# SmoothieDriverDualDC.net
KiCad netlist of a schematic drawn in EAGLE
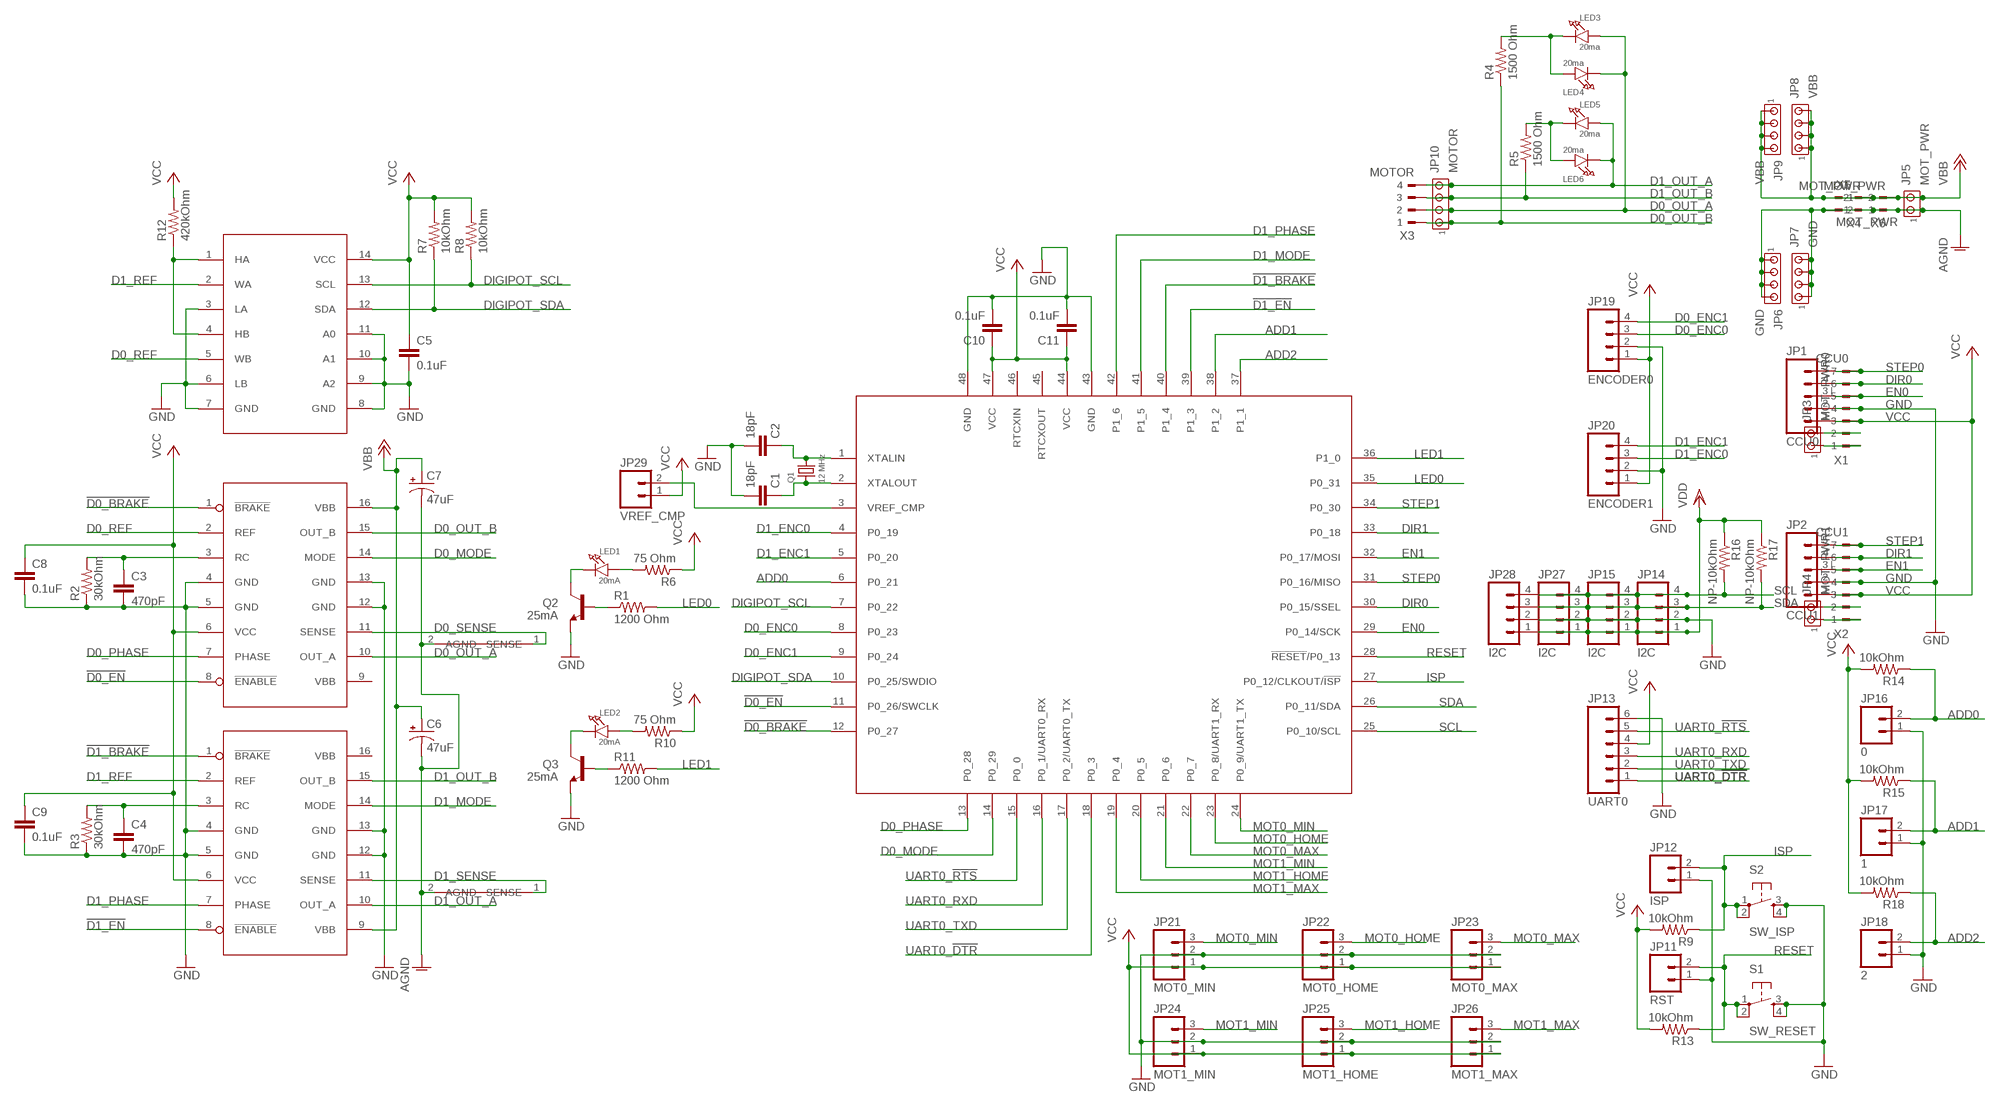
[diagram p0: schematic, sheet 1]

(export (version "E")
  (design (tool "Eeschema 10.0.6"))
  (components
    (comp (ref "C1")
      (value "18pF")
      (footprint "eagle-import:C0603")
      (libsource (lib "eagle-import") (part "C-EUC0603"))
    )
    (comp (ref "C2")
      (value "18pF")
      (footprint "eagle-import:C0603")
      (libsource (lib "eagle-import") (part "C-EUC0603"))
    )
    (comp (ref "C3")
      (value "470pF")
      (footprint "eagle-import:C0603")
      (libsource (lib "eagle-import") (part "C-EUC0603"))
    )
    (comp (ref "C4")
      (value "470pF")
      (footprint "eagle-import:C0603")
      (libsource (lib "eagle-import") (part "C-EUC0603"))
    )
    (comp (ref "C5")
      (value "0.1uF")
      (footprint "eagle-import:C0603")
      (libsource (lib "eagle-import") (part "C-EUC0603"))
    )
    (comp (ref "C6")
      (value "47uF")
      (footprint "eagle-import:PANASONIC_D")
      (libsource (lib "eagle-import") (part "CAP_POLD"))
    )
    (comp (ref "C7")
      (value "47uF")
      (footprint "eagle-import:PANASONIC_D")
      (libsource (lib "eagle-import") (part "CAP_POLD"))
    )
    (comp (ref "C8")
      (value "0.1uF")
      (footprint "eagle-import:C0603")
      (libsource (lib "eagle-import") (part "C-EUC0603"))
    )
    (comp (ref "C9")
      (value "0.1uF")
      (footprint "eagle-import:C0603")
      (libsource (lib "eagle-import") (part "C-EUC0603"))
    )
    (comp (ref "C10")
      (value "0.1uF")
      (footprint "eagle-import:C0603")
      (libsource (lib "eagle-import") (part "C-EUC0603"))
    )
    (comp (ref "C11")
      (value "0.1uF")
      (footprint "eagle-import:C0603")
      (libsource (lib "eagle-import") (part "C-EUC0603"))
    )
    (comp (ref "JP1")
      (value "CCU0")
      (footprint "eagle-import:1X05")
      (libsource (lib "eagle-import") (part "M05PTH"))
    )
    (comp (ref "JP2")
      (value "CCU1")
      (footprint "eagle-import:1X05")
      (libsource (lib "eagle-import") (part "M05PTH"))
    )
    (comp (ref "JP3")
      (value "MOT_PWR0")
      (footprint "eagle-import:10X02MTA")
      (libsource (lib "eagle-import") (part "MTA02-100"))
    )
    (comp (ref "JP4")
      (value "MOT_PWR1")
      (footprint "eagle-import:10X02MTA")
      (libsource (lib "eagle-import") (part "MTA02-100"))
    )
    (comp (ref "JP5")
      (value "MOT_PWR")
      (footprint "eagle-import:10X02MTA")
      (libsource (lib "eagle-import") (part "MTA02-100"))
    )
    (comp (ref "JP6")
      (value "GND")
      (footprint "eagle-import:10X04MTA")
      (libsource (lib "eagle-import") (part "MTA04-100"))
    )
    (comp (ref "JP7")
      (value "GND")
      (footprint "eagle-import:10X04MTA")
      (libsource (lib "eagle-import") (part "MTA04-100"))
    )
    (comp (ref "JP8")
      (value "VBB")
      (footprint "eagle-import:10X04MTA")
      (libsource (lib "eagle-import") (part "MTA04-100"))
    )
    (comp (ref "JP9")
      (value "VBB")
      (footprint "eagle-import:10X04MTA")
      (libsource (lib "eagle-import") (part "MTA04-100"))
    )
    (comp (ref "JP10")
      (value "MOTOR")
      (footprint "eagle-import:10X04MTA")
      (libsource (lib "eagle-import") (part "MTA04-100"))
    )
    (comp (ref "JP11")
      (value "RST")
      (footprint "eagle-import:1X02")
      (libsource (lib "eagle-import") (part "M02PTH"))
    )
    (comp (ref "JP12")
      (value "ISP")
      (footprint "eagle-import:1X02")
      (libsource (lib "eagle-import") (part "M02PTH"))
    )
    (comp (ref "JP13")
      (value "UART0")
      (footprint "eagle-import:1X06")
      (libsource (lib "eagle-import") (part "M06SIP"))
    )
    (comp (ref "JP14")
      (value "I2C")
      (footprint "eagle-import:1X04")
      (libsource (lib "eagle-import") (part "M04PTH"))
    )
    (comp (ref "JP15")
      (value "I2C")
      (footprint "eagle-import:1X04")
      (libsource (lib "eagle-import") (part "M04PTH"))
    )
    (comp (ref "JP16")
      (value "0")
      (footprint "eagle-import:1X02")
      (libsource (lib "eagle-import") (part "M02PTH"))
    )
    (comp (ref "JP17")
      (value "1")
      (footprint "eagle-import:1X02")
      (libsource (lib "eagle-import") (part "M02PTH"))
    )
    (comp (ref "JP18")
      (value "2")
      (footprint "eagle-import:1X02")
      (libsource (lib "eagle-import") (part "M02PTH"))
    )
    (comp (ref "JP19")
      (value "ENCODER0")
      (footprint "eagle-import:1X04")
      (libsource (lib "eagle-import") (part "M04PTH"))
    )
    (comp (ref "JP20")
      (value "ENCODER1")
      (footprint "eagle-import:1X04")
      (libsource (lib "eagle-import") (part "M04PTH"))
    )
    (comp (ref "JP21")
      (value "MOT0_MIN")
      (footprint "eagle-import:1X03")
      (libsource (lib "eagle-import") (part "M03PTH"))
    )
    (comp (ref "JP22")
      (value "MOT0_HOME")
      (footprint "eagle-import:1X03")
      (libsource (lib "eagle-import") (part "M03PTH"))
    )
    (comp (ref "JP23")
      (value "MOT0_MAX")
      (footprint "eagle-import:1X03")
      (libsource (lib "eagle-import") (part "M03PTH"))
    )
    (comp (ref "JP24")
      (value "MOT1_MIN")
      (footprint "eagle-import:1X03")
      (libsource (lib "eagle-import") (part "M03PTH"))
    )
    (comp (ref "JP25")
      (value "MOT1_HOME")
      (footprint "eagle-import:1X03")
      (libsource (lib "eagle-import") (part "M03PTH"))
    )
    (comp (ref "JP26")
      (value "MOT1_MAX")
      (footprint "eagle-import:1X03")
      (libsource (lib "eagle-import") (part "M03PTH"))
    )
    (comp (ref "JP27")
      (value "I2C")
      (footprint "eagle-import:1X04")
      (libsource (lib "eagle-import") (part "M04PTH"))
    )
    (comp (ref "JP28")
      (value "I2C")
      (footprint "eagle-import:1X04")
      (libsource (lib "eagle-import") (part "M04PTH"))
    )
    (comp (ref "JP29")
      (value "VREF_CMP")
      (footprint "eagle-import:1X02")
      (libsource (lib "eagle-import") (part "M02PTH"))
    )
    (comp (ref "LED1")
      (value "20mA")
      (footprint "eagle-import:CHIPLED_0805")
      (libsource (lib "eagle-import") (part "LED0805"))
    )
    (comp (ref "LED2")
      (value "20mA")
      (footprint "eagle-import:CHIPLED_0805")
      (libsource (lib "eagle-import") (part "LED0805"))
    )
    (comp (ref "LED3")
      (value "20ma")
      (footprint "eagle-import:CHIPLED_0805")
      (libsource (lib "eagle-import") (part "LED0805"))
    )
    (comp (ref "LED4")
      (value "20ma")
      (footprint "eagle-import:CHIPLED_0805")
      (libsource (lib "eagle-import") (part "LED0805"))
    )
    (comp (ref "LED5")
      (value "20ma")
      (footprint "eagle-import:CHIPLED_0805")
      (libsource (lib "eagle-import") (part "LED0805"))
    )
    (comp (ref "LED6")
      (value "20ma")
      (footprint "eagle-import:CHIPLED_0805")
      (libsource (lib "eagle-import") (part "LED0805"))
    )
    (comp (ref "MCU1")
      (value "LPC1227")
      (footprint "eagle-import:LQFP48")
      (libsource (lib "eagle-import") (part "LPC1227"))
    )
    (comp (ref "Q1")
      (value "12 MHz")
      (footprint "eagle-import:CRYSTAL_3.2X2.5")
      (libsource (lib "eagle-import") (part "CRYSTALTHIN"))
    )
    (comp (ref "Q2")
      (value "25mA")
      (footprint "eagle-import:SOT23")
      (libsource (lib "eagle-import") (part "TRANSISTOR_NPNSOT23"))
    )
    (comp (ref "Q3")
      (value "25mA")
      (footprint "eagle-import:SOT23")
      (libsource (lib "eagle-import") (part "TRANSISTOR_NPNSOT23"))
    )
    (comp (ref "R1")
      (value "1200 Ohm")
      (footprint "eagle-import:R0603")
      (libsource (lib "eagle-import") (part "R-US_R0603"))
    )
    (comp (ref "R2")
      (value "30kOhm")
      (footprint "eagle-import:R0603")
      (libsource (lib "eagle-import") (part "R-US_R0603"))
    )
    (comp (ref "R3")
      (value "30kOhm")
      (footprint "eagle-import:R0603")
      (libsource (lib "eagle-import") (part "R-US_R0603"))
    )
    (comp (ref "R4")
      (value "1500 Ohm")
      (footprint "eagle-import:R0603")
      (libsource (lib "eagle-import") (part "R-US_R0603"))
    )
    (comp (ref "R5")
      (value "1500 Ohm")
      (footprint "eagle-import:R0603")
      (libsource (lib "eagle-import") (part "R-US_R0603"))
    )
    (comp (ref "R6")
      (value "75 Ohm")
      (footprint "eagle-import:R0603")
      (libsource (lib "eagle-import") (part "R-US_R0603"))
    )
    (comp (ref "R7")
      (value "10kOhm")
      (footprint "eagle-import:R0603")
      (libsource (lib "eagle-import") (part "R-US_R0603"))
    )
    (comp (ref "R8")
      (value "10kOhm")
      (footprint "eagle-import:R0603")
      (libsource (lib "eagle-import") (part "R-US_R0603"))
    )
    (comp (ref "R9")
      (value "10kOhm")
      (footprint "eagle-import:R0603")
      (libsource (lib "eagle-import") (part "R-US_R0603"))
    )
    (comp (ref "R10")
      (value "75 Ohm")
      (footprint "eagle-import:R0603")
      (libsource (lib "eagle-import") (part "R-US_R0603"))
    )
    (comp (ref "R11")
      (value "1200 Ohm")
      (footprint "eagle-import:R0603")
      (libsource (lib "eagle-import") (part "R-US_R0603"))
    )
    (comp (ref "R12")
      (value "420kOhm")
      (footprint "eagle-import:R0603")
      (libsource (lib "eagle-import") (part "R-US_R0603"))
    )
    (comp (ref "R13")
      (value "10kOhm")
      (footprint "eagle-import:R0603")
      (libsource (lib "eagle-import") (part "R-US_R0603"))
    )
    (comp (ref "R14")
      (value "10kOhm")
      (footprint "eagle-import:R0603")
      (libsource (lib "eagle-import") (part "R-US_R0603"))
    )
    (comp (ref "R15")
      (value "10kOhm")
      (footprint "eagle-import:R0603")
      (libsource (lib "eagle-import") (part "R-US_R0603"))
    )
    (comp (ref "R16")
      (value "NP-10kOhm")
      (footprint "eagle-import:R0603")
      (libsource (lib "eagle-import") (part "R-US_R0603"))
    )
    (comp (ref "R17")
      (value "NP-10kOhm")
      (footprint "eagle-import:R0603")
      (libsource (lib "eagle-import") (part "R-US_R0603"))
    )
    (comp (ref "R18")
      (value "10kOhm")
      (footprint "eagle-import:R0603")
      (libsource (lib "eagle-import") (part "R-US_R0603"))
    )
    (comp (ref "S1")
      (value "SW_RESET")
      (footprint "eagle-import:TACTILE_SWITCH_SMD")
      (libsource (lib "eagle-import") (part "TAC_SWITCHSMD"))
    )
    (comp (ref "S2")
      (value "SW_ISP")
      (footprint "eagle-import:TACTILE_SWITCH_SMD")
      (libsource (lib "eagle-import") (part "TAC_SWITCHSMD"))
    )
    (comp (ref "U$1")
      (value "CONNECTOR")
      (footprint "eagle-import:CONNECT")
      (libsource (lib "eagle-import") (part "CONNECTOR"))
    )
    (comp (ref "U$2")
      (value "CONNECTOR")
      (footprint "eagle-import:CONNECT")
      (libsource (lib "eagle-import") (part "CONNECTOR"))
    )
    (comp (ref "U1")
      (value "MAX5387-50kOhm")
      (footprint "eagle-import:TSSOP14")
      (libsource (lib "eagle-import") (part "MAX5387"))
    )
    (comp (ref "U2")
      (value "A4973")
      (footprint "eagle-import:SO16L")
      (libsource (lib "eagle-import") (part "A4973"))
    )
    (comp (ref "U3")
      (value "A4973")
      (footprint "eagle-import:SO16L")
      (libsource (lib "eagle-import") (part "A4973"))
    )
    (comp (ref "X1")
      (value "CCU0")
      (footprint "eagle-import:180G-7")
      (libsource (lib "eagle-import") (part "180G-7"))
    )
    (comp (ref "X2")
      (value "CCU1")
      (footprint "eagle-import:180G-7")
      (libsource (lib "eagle-import") (part "180G-7"))
    )
    (comp (ref "X3")
      (value "MOTOR")
      (footprint "eagle-import:180G-4")
      (libsource (lib "eagle-import") (part "180G-4"))
    )
    (comp (ref "X4")
      (value "MOT_PWR")
      (footprint "eagle-import:180G-2")
      (fields (field (name "OC_FARNELL") "unknown") (field (name "OC_NEWARK") "unknown"))
      (libsource (lib "eagle-import") (part "180G-2"))
    )
    (comp (ref "X5")
      (value "MOT_PWR")
      (footprint "eagle-import:180G-2")
      (fields (field (name "OC_FARNELL") "unknown") (field (name "OC_NEWARK") "unknown"))
      (libsource (lib "eagle-import") (part "180G-2"))
    )
    (comp (ref "X6")
      (value "MOT_PWR")
      (footprint "eagle-import:180G-2")
      (libsource (lib "eagle-import") (part "180G-2"))
    )
  )
  (nets
    (net (code "1") (name "/ADD0") (class "Default")
      (node (ref "JP16") (pin "2") (pinfunction "2_2") (pintype "passive"))
      (node (ref "MCU1") (pin "6") (pinfunction "P0_21_6") (pintype "bidirectional"))
      (node (ref "R14") (pin "1") (pinfunction "1_1") (pintype "passive"))
    )
    (net (code "2") (name "/ADD1") (class "Default")
      (node (ref "JP17") (pin "2") (pinfunction "2_2") (pintype "passive"))
      (node (ref "MCU1") (pin "38") (pinfunction "P1_2_38") (pintype "bidirectional"))
      (node (ref "R15") (pin "1") (pinfunction "1_1") (pintype "passive"))
    )
    (net (code "3") (name "/ADD2") (class "Default")
      (node (ref "JP18") (pin "2") (pinfunction "2_2") (pintype "passive"))
      (node (ref "MCU1") (pin "37") (pinfunction "P1_1_37") (pintype "bidirectional"))
      (node (ref "R18") (pin "1") (pinfunction "1_1") (pintype "passive"))
    )
    (net (code "4") (name "/D0_ENC0") (class "Default")
      (node (ref "JP19") (pin "3") (pinfunction "3_3") (pintype "passive"))
      (node (ref "MCU1") (pin "8") (pinfunction "P0_23_8") (pintype "bidirectional"))
    )
    (net (code "5") (name "/D0_ENC1") (class "Default")
      (node (ref "JP19") (pin "4") (pinfunction "4_4") (pintype "passive"))
      (node (ref "MCU1") (pin "9") (pinfunction "P0_24_9") (pintype "bidirectional"))
    )
    (net (code "6") (name "/D0_MODE") (class "Default")
      (node (ref "MCU1") (pin "14") (pinfunction "P0_29_14") (pintype "bidirectional"))
      (node (ref "U2") (pin "14") (pinfunction "MODE_14") (pintype "input"))
    )
    (net (code "7") (name "/D0_OUT_A") (class "Default")
      (node (ref "JP10") (pin "2") (pinfunction "2_2") (pintype "passive"))
      (node (ref "LED3") (pin "A") (pinfunction "A_A") (pintype "passive"))
      (node (ref "LED4") (pin "C") (pinfunction "C_C") (pintype "passive"))
      (node (ref "U2") (pin "10") (pinfunction "OUT_A_10") (pintype "output"))
      (node (ref "X3") (pin "2") (pinfunction "2_2") (pintype "passive"))
    )
    (net (code "8") (name "/D0_OUT_B") (class "Default")
      (node (ref "JP10") (pin "1") (pinfunction "1_1") (pintype "passive"))
      (node (ref "R4") (pin "1") (pinfunction "1_1") (pintype "passive"))
      (node (ref "U2") (pin "15") (pinfunction "OUT_B_15") (pintype "output"))
      (node (ref "X3") (pin "1") (pinfunction "1_1") (pintype "passive"))
    )
    (net (code "9") (name "/D0_PHASE") (class "Default")
      (node (ref "MCU1") (pin "13") (pinfunction "P0_28_13") (pintype "bidirectional"))
      (node (ref "U2") (pin "7") (pinfunction "PHASE_7") (pintype "input"))
    )
    (net (code "10") (name "/D0_REF") (class "Default")
      (node (ref "U1") (pin "5") (pinfunction "WB_5") (pintype "passive"))
      (node (ref "U2") (pin "2") (pinfunction "REF_2") (pintype "input"))
    )
    (net (code "11") (name "/D0_SENSE") (class "Default")
      (node (ref "U$2") (pin "1") (pinfunction "SENSE_1") (pintype "bidirectional"))
      (node (ref "U2") (pin "11") (pinfunction "SENSE_11") (pintype "bidirectional"))
    )
    (net (code "12") (name "/D1_ENC0") (class "Default")
      (node (ref "JP20") (pin "3") (pinfunction "3_3") (pintype "passive"))
      (node (ref "MCU1") (pin "4") (pinfunction "P0_19_4") (pintype "bidirectional"))
    )
    (net (code "13") (name "/D1_ENC1") (class "Default")
      (node (ref "JP20") (pin "4") (pinfunction "4_4") (pintype "passive"))
      (node (ref "MCU1") (pin "5") (pinfunction "P0_20_5") (pintype "bidirectional"))
    )
    (net (code "14") (name "/D1_MODE") (class "Default")
      (node (ref "MCU1") (pin "41") (pinfunction "P1_5_41") (pintype "bidirectional"))
      (node (ref "U3") (pin "14") (pinfunction "MODE_14") (pintype "input"))
    )
    (net (code "15") (name "/D1_OUT_A") (class "Default")
      (node (ref "JP10") (pin "4") (pinfunction "4_4") (pintype "passive"))
      (node (ref "LED5") (pin "A") (pinfunction "A_A") (pintype "passive"))
      (node (ref "LED6") (pin "C") (pinfunction "C_C") (pintype "passive"))
      (node (ref "U3") (pin "10") (pinfunction "OUT_A_10") (pintype "output"))
      (node (ref "X3") (pin "4") (pinfunction "4_4") (pintype "passive"))
    )
    (net (code "16") (name "/D1_OUT_B") (class "Default")
      (node (ref "JP10") (pin "3") (pinfunction "3_3") (pintype "passive"))
      (node (ref "R5") (pin "1") (pinfunction "1_1") (pintype "passive"))
      (node (ref "U3") (pin "15") (pinfunction "OUT_B_15") (pintype "output"))
      (node (ref "X3") (pin "3") (pinfunction "3_3") (pintype "passive"))
    )
    (net (code "17") (name "/D1_PHASE") (class "Default")
      (node (ref "MCU1") (pin "42") (pinfunction "P1_6_42") (pintype "bidirectional"))
      (node (ref "U3") (pin "7") (pinfunction "PHASE_7") (pintype "input"))
    )
    (net (code "18") (name "/D1_REF") (class "Default")
      (node (ref "U1") (pin "2") (pinfunction "WA_2") (pintype "passive"))
      (node (ref "U3") (pin "2") (pinfunction "REF_2") (pintype "input"))
    )
    (net (code "19") (name "/D1_SENSE") (class "Default")
      (node (ref "U$1") (pin "1") (pinfunction "SENSE_1") (pintype "bidirectional"))
      (node (ref "U3") (pin "11") (pinfunction "SENSE_11") (pintype "bidirectional"))
    )
    (net (code "20") (name "/DIGIPOT_SCL") (class "Default")
      (node (ref "MCU1") (pin "7") (pinfunction "P0_22_7") (pintype "bidirectional"))
      (node (ref "R8") (pin "1") (pinfunction "1_1") (pintype "passive"))
      (node (ref "U1") (pin "13") (pinfunction "SCL_13") (pintype "input"))
    )
    (net (code "21") (name "/DIGIPOT_SDA") (class "Default")
      (node (ref "MCU1") (pin "10") (pinfunction "P0_25/SWDIO_10") (pintype "bidirectional"))
      (node (ref "R7") (pin "1") (pinfunction "1_1") (pintype "passive"))
      (node (ref "U1") (pin "12") (pinfunction "SDA_12") (pintype "bidirectional"))
    )
    (net (code "22") (name "/DIR0") (class "Default")
      (node (ref "JP1") (pin "4") (pinfunction "4_4") (pintype "passive"))
      (node (ref "MCU1") (pin "30") (pinfunction "P0_15/SSEL_30") (pintype "bidirectional"))
      (node (ref "X1") (pin "6") (pinfunction "6_6") (pintype "passive"))
    )
    (net (code "23") (name "/DIR1") (class "Default")
      (node (ref "JP2") (pin "4") (pinfunction "4_4") (pintype "passive"))
      (node (ref "MCU1") (pin "33") (pinfunction "P0_18_33") (pintype "bidirectional"))
      (node (ref "X2") (pin "6") (pinfunction "6_6") (pintype "passive"))
    )
    (net (code "24") (name "/EN0") (class "Default")
      (node (ref "JP1") (pin "3") (pinfunction "3_3") (pintype "passive"))
      (node (ref "MCU1") (pin "29") (pinfunction "P0_14/SCK_29") (pintype "bidirectional"))
      (node (ref "X1") (pin "5") (pinfunction "5_5") (pintype "passive"))
    )
    (net (code "25") (name "/EN1") (class "Default")
      (node (ref "JP2") (pin "3") (pinfunction "3_3") (pintype "passive"))
      (node (ref "MCU1") (pin "32") (pinfunction "P0_17/MOSI_32") (pintype "bidirectional"))
      (node (ref "X2") (pin "5") (pinfunction "5_5") (pintype "passive"))
    )
    (net (code "26") (name "/ISP") (class "Default")
      (node (ref "JP12") (pin "2") (pinfunction "2_2") (pintype "passive"))
      (node (ref "MCU1") (pin "27") (pinfunction "P0_12/CLKOUT/~{ISP}_27") (pintype "bidirectional"))
      (node (ref "R9") (pin "1") (pinfunction "1_1") (pintype "passive"))
      (node (ref "S2") (pin "1") (pinfunction "1_1") (pintype "passive"))
      (node (ref "S2") (pin "2") (pinfunction "2_2") (pintype "passive"))
    )
    (net (code "27") (name "/LED0") (class "Default")
      (node (ref "MCU1") (pin "35") (pinfunction "P0_31_35") (pintype "bidirectional"))
      (node (ref "R1") (pin "2") (pinfunction "2_2") (pintype "passive"))
    )
    (net (code "28") (name "/LED1") (class "Default")
      (node (ref "MCU1") (pin "36") (pinfunction "P1_0_36") (pintype "bidirectional"))
      (node (ref "R11") (pin "2") (pinfunction "2_2") (pintype "passive"))
    )
    (net (code "29") (name "/MOT0_HOME") (class "Default")
      (node (ref "JP22") (pin "3") (pinfunction "3_3") (pintype "passive"))
      (node (ref "MCU1") (pin "23") (pinfunction "P0_8/UART1_RX_23") (pintype "bidirectional"))
    )
    (net (code "30") (name "/MOT0_MAX") (class "Default")
      (node (ref "JP23") (pin "3") (pinfunction "3_3") (pintype "passive"))
      (node (ref "MCU1") (pin "22") (pinfunction "P0_7_22") (pintype "bidirectional"))
    )
    (net (code "31") (name "/MOT0_MIN") (class "Default")
      (node (ref "JP21") (pin "3") (pinfunction "3_3") (pintype "passive"))
      (node (ref "MCU1") (pin "24") (pinfunction "P0_9/UART1_TX_24") (pintype "bidirectional"))
    )
    (net (code "32") (name "/MOT1_HOME") (class "Default")
      (node (ref "JP25") (pin "3") (pinfunction "3_3") (pintype "passive"))
      (node (ref "MCU1") (pin "20") (pinfunction "P0_5_20") (pintype "bidirectional"))
    )
    (net (code "33") (name "/MOT1_MAX") (class "Default")
      (node (ref "JP26") (pin "3") (pinfunction "3_3") (pintype "passive"))
      (node (ref "MCU1") (pin "19") (pinfunction "P0_4_19") (pintype "bidirectional"))
    )
    (net (code "34") (name "/MOT1_MIN") (class "Default")
      (node (ref "JP24") (pin "3") (pinfunction "3_3") (pintype "passive"))
      (node (ref "MCU1") (pin "21") (pinfunction "P0_6_21") (pintype "bidirectional"))
    )
    (net (code "35") (name "/RESET") (class "Default")
      (node (ref "JP11") (pin "2") (pinfunction "2_2") (pintype "passive"))
      (node (ref "MCU1") (pin "28") (pinfunction "~{RESET}/P0_13_28") (pintype "bidirectional"))
      (node (ref "R13") (pin "1") (pinfunction "1_1") (pintype "passive"))
      (node (ref "S1") (pin "1") (pinfunction "1_1") (pintype "passive"))
      (node (ref "S1") (pin "2") (pinfunction "2_2") (pintype "passive"))
    )
    (net (code "36") (name "/SCL") (class "Default")
      (node (ref "JP14") (pin "4") (pinfunction "4_4") (pintype "passive"))
      (node (ref "JP15") (pin "4") (pinfunction "4_4") (pintype "passive"))
      (node (ref "JP27") (pin "4") (pinfunction "4_4") (pintype "passive"))
      (node (ref "JP28") (pin "4") (pinfunction "4_4") (pintype "passive"))
      (node (ref "MCU1") (pin "25") (pinfunction "P0_10/SCL_25") (pintype "bidirectional"))
      (node (ref "R16") (pin "2") (pinfunction "2_2") (pintype "passive"))
    )
    (net (code "37") (name "/SDA") (class "Default")
      (node (ref "JP14") (pin "3") (pinfunction "3_3") (pintype "passive"))
      (node (ref "JP15") (pin "3") (pinfunction "3_3") (pintype "passive"))
      (node (ref "JP27") (pin "3") (pinfunction "3_3") (pintype "passive"))
      (node (ref "JP28") (pin "3") (pinfunction "3_3") (pintype "passive"))
      (node (ref "MCU1") (pin "26") (pinfunction "P0_11/SDA_26") (pintype "bidirectional"))
      (node (ref "R17") (pin "2") (pinfunction "2_2") (pintype "passive"))
    )
    (net (code "38") (name "/STEP0") (class "Default")
      (node (ref "JP1") (pin "5") (pinfunction "5_5") (pintype "passive"))
      (node (ref "MCU1") (pin "31") (pinfunction "P0_16/MISO_31") (pintype "bidirectional"))
      (node (ref "X1") (pin "7") (pinfunction "7_7") (pintype "passive"))
    )
    (net (code "39") (name "/STEP1") (class "Default")
      (node (ref "JP2") (pin "5") (pinfunction "5_5") (pintype "passive"))
      (node (ref "MCU1") (pin "34") (pinfunction "P0_30_34") (pintype "bidirectional"))
      (node (ref "X2") (pin "7") (pinfunction "7_7") (pintype "passive"))
    )
    (net (code "40") (name "/UART0_RXD") (class "Default")
      (node (ref "JP13") (pin "3") (pinfunction "3_3") (pintype "passive"))
      (node (ref "MCU1") (pin "16") (pinfunction "P0_1/UART0_RX_16") (pintype "bidirectional"))
    )
    (net (code "41") (name "/UART0_TXD") (class "Default")
      (node (ref "JP13") (pin "2") (pinfunction "2_2") (pintype "passive"))
      (node (ref "MCU1") (pin "17") (pinfunction "P0_2/UART0_TX_17") (pintype "bidirectional"))
    )
    (net (code "42") (name "/UART0_~{DTR}") (class "Default")
      (node (ref "JP13") (pin "1") (pinfunction "1_1") (pintype "passive"))
      (node (ref "MCU1") (pin "18") (pinfunction "P0_3_18") (pintype "bidirectional"))
    )
    (net (code "43") (name "/UART0_~{RTS}") (class "Default")
      (node (ref "JP13") (pin "5") (pinfunction "5_5") (pintype "passive"))
      (node (ref "MCU1") (pin "15") (pinfunction "P0_0_15") (pintype "bidirectional"))
    )
    (net (code "44") (name "/~{D0_BRAKE}") (class "Default")
      (node (ref "MCU1") (pin "12") (pinfunction "P0_27_12") (pintype "bidirectional"))
      (node (ref "U2") (pin "1") (pinfunction "~{BRAKE}_1") (pintype "input"))
    )
    (net (code "45") (name "/~{D0_EN}") (class "Default")
      (node (ref "MCU1") (pin "11") (pinfunction "P0_26/SWCLK_11") (pintype "bidirectional"))
      (node (ref "U2") (pin "8") (pinfunction "~{ENABLE}_8") (pintype "input"))
    )
    (net (code "46") (name "/~{D1_BRAKE}") (class "Default")
      (node (ref "MCU1") (pin "40") (pinfunction "P1_4_40") (pintype "bidirectional"))
      (node (ref "U3") (pin "1") (pinfunction "~{BRAKE}_1") (pintype "input"))
    )
    (net (code "47") (name "/~{D1_EN}") (class "Default")
      (node (ref "MCU1") (pin "39") (pinfunction "P1_3_39") (pintype "bidirectional"))
      (node (ref "U3") (pin "8") (pinfunction "~{ENABLE}_8") (pintype "input"))
    )
    (net (code "48") (name "AGND") (class "Default")
      (node (ref "C6") (pin "-") (pinfunction "-_-") (pintype "passive"))
      (node (ref "C7") (pin "-") (pinfunction "-_-") (pintype "passive"))
      (node (ref "JP5") (pin "1") (pinfunction "1_1") (pintype "passive"))
      (node (ref "JP6") (pin "1") (pinfunction "1_1") (pintype "passive"))
      (node (ref "JP6") (pin "2") (pinfunction "2_2") (pintype "passive"))
      (node (ref "JP6") (pin "3") (pinfunction "3_3") (pintype "passive"))
      (node (ref "JP6") (pin "4") (pinfunction "4_4") (pintype "passive"))
      (node (ref "JP7") (pin "1") (pinfunction "1_1") (pintype "passive"))
      (node (ref "JP7") (pin "2") (pinfunction "2_2") (pintype "passive"))
      (node (ref "JP7") (pin "3") (pinfunction "3_3") (pintype "passive"))
      (node (ref "JP7") (pin "4") (pinfunction "4_4") (pintype "passive"))
      (node (ref "U$1") (pin "2") (pinfunction "AGND_2") (pintype "power_in"))
      (node (ref "U$2") (pin "2") (pinfunction "AGND_2") (pintype "power_in"))
      (node (ref "X4") (pin "1") (pinfunction "1_1") (pintype "passive"))
      (node (ref "X5") (pin "2") (pinfunction "2_2") (pintype "passive"))
      (node (ref "X6") (pin "1") (pinfunction "1_1") (pintype "passive"))
    )
    (net (code "49") (name "GND") (class "Default")
      (node (ref "C1") (pin "2") (pinfunction "2_2") (pintype "passive"))
      (node (ref "C10") (pin "2") (pinfunction "2_2") (pintype "passive"))
      (node (ref "C11") (pin "2") (pinfunction "2_2") (pintype "passive"))
      (node (ref "C2") (pin "2") (pinfunction "2_2") (pintype "passive"))
      (node (ref "C3") (pin "2") (pinfunction "2_2") (pintype "passive"))
      (node (ref "C4") (pin "2") (pinfunction "2_2") (pintype "passive"))
      (node (ref "C5") (pin "2") (pinfunction "2_2") (pintype "passive"))
      (node (ref "C8") (pin "2") (pinfunction "2_2") (pintype "passive"))
      (node (ref "C9") (pin "2") (pinfunction "2_2") (pintype "passive"))
      (node (ref "JP1") (pin "2") (pinfunction "2_2") (pintype "passive"))
      (node (ref "JP11") (pin "1") (pinfunction "1_1") (pintype "passive"))
      (node (ref "JP12") (pin "1") (pinfunction "1_1") (pintype "passive"))
      (node (ref "JP13") (pin "6") (pinfunction "6_6") (pintype "passive"))
      (node (ref "JP14") (pin "2") (pinfunction "2_2") (pintype "passive"))
      (node (ref "JP15") (pin "2") (pinfunction "2_2") (pintype "passive"))
      (node (ref "JP16") (pin "1") (pinfunction "1_1") (pintype "passive"))
      (node (ref "JP17") (pin "1") (pinfunction "1_1") (pintype "passive"))
      (node (ref "JP18") (pin "1") (pinfunction "1_1") (pintype "passive"))
      (node (ref "JP19") (pin "2") (pinfunction "2_2") (pintype "passive"))
      (node (ref "JP2") (pin "2") (pinfunction "2_2") (pintype "passive"))
      (node (ref "JP20") (pin "2") (pinfunction "2_2") (pintype "passive"))
      (node (ref "JP21") (pin "2") (pinfunction "2_2") (pintype "passive"))
      (node (ref "JP22") (pin "2") (pinfunction "2_2") (pintype "passive"))
      (node (ref "JP23") (pin "2") (pinfunction "2_2") (pintype "passive"))
      (node (ref "JP24") (pin "2") (pinfunction "2_2") (pintype "passive"))
      (node (ref "JP25") (pin "2") (pinfunction "2_2") (pintype "passive"))
      (node (ref "JP26") (pin "2") (pinfunction "2_2") (pintype "passive"))
      (node (ref "JP27") (pin "2") (pinfunction "2_2") (pintype "passive"))
      (node (ref "JP28") (pin "2") (pinfunction "2_2") (pintype "passive"))
      (node (ref "MCU1") (pin "43") (pinfunction "GND_43") (pintype "power_in"))
      (node (ref "MCU1") (pin "48") (pinfunction "GND_48") (pintype "power_in"))
      (node (ref "Q2") (pin "2") (pinfunction "E_2") (pintype "passive"))
      (node (ref "Q3") (pin "2") (pinfunction "E_2") (pintype "passive"))
      (node (ref "R2") (pin "1") (pinfunction "1_1") (pintype "passive"))
      (node (ref "R3") (pin "1") (pinfunction "1_1") (pintype "passive"))
      (node (ref "S1") (pin "3") (pinfunction "3_3") (pintype "passive"))
      (node (ref "S1") (pin "4") (pinfunction "4_4") (pintype "passive"))
      (node (ref "S2") (pin "3") (pinfunction "3_3") (pintype "passive"))
      (node (ref "S2") (pin "4") (pinfunction "4_4") (pintype "passive"))
      (node (ref "U1") (pin "10") (pinfunction "A1_10") (pintype "input"))
      (node (ref "U1") (pin "11") (pinfunction "A0_11") (pintype "input"))
      (node (ref "U1") (pin "3") (pinfunction "LA_3") (pintype "passive"))
      (node (ref "U1") (pin "6") (pinfunction "LB_6") (pintype "passive"))
      (node (ref "U1") (pin "7") (pinfunction "GND_7") (pintype "power_in"))
      (node (ref "U1") (pin "8") (pinfunction "GND_8") (pintype "power_in"))
      (node (ref "U1") (pin "9") (pinfunction "A2_9") (pintype "input"))
      (node (ref "U2") (pin "12") (pinfunction "GND_12") (pintype "power_in"))
      (node (ref "U2") (pin "13") (pinfunction "GND_13") (pintype "power_in"))
      (node (ref "U2") (pin "4") (pinfunction "GND_4") (pintype "power_in"))
      (node (ref "U2") (pin "5") (pinfunction "GND_5") (pintype "power_in"))
      (node (ref "U3") (pin "12") (pinfunction "GND_12") (pintype "power_in"))
      (node (ref "U3") (pin "13") (pinfunction "GND_13") (pintype "power_in"))
      (node (ref "U3") (pin "4") (pinfunction "GND_4") (pintype "power_in"))
      (node (ref "U3") (pin "5") (pinfunction "GND_5") (pintype "power_in"))
      (node (ref "X1") (pin "4") (pinfunction "4_4") (pintype "passive"))
      (node (ref "X2") (pin "4") (pinfunction "4_4") (pintype "passive"))
    )
    (net (code "50") (name "Net-(JP3-Pad1)") (class "Default")
      (node (ref "JP3") (pin "1") (pinfunction "1_1") (pintype "passive"))
      (node (ref "X1") (pin "1") (pinfunction "1_1") (pintype "passive"))
    )
    (net (code "51") (name "Net-(JP3-Pad2)") (class "Default")
      (node (ref "JP3") (pin "2") (pinfunction "2_2") (pintype "passive"))
      (node (ref "X1") (pin "2") (pinfunction "2_2") (pintype "passive"))
    )
    (net (code "52") (name "Net-(JP4-Pad1)") (class "Default")
      (node (ref "JP4") (pin "1") (pinfunction "1_1") (pintype "passive"))
      (node (ref "X2") (pin "1") (pinfunction "1_1") (pintype "passive"))
    )
    (net (code "53") (name "Net-(JP4-Pad2)") (class "Default")
      (node (ref "JP4") (pin "2") (pinfunction "2_2") (pintype "passive"))
      (node (ref "X2") (pin "2") (pinfunction "2_2") (pintype "passive"))
    )
    (net (code "54") (name "Net-(LED1-PadA)") (class "Default")
      (node (ref "LED1") (pin "A") (pinfunction "A_A") (pintype "passive"))
      (node (ref "R6") (pin "2") (pinfunction "2_2") (pintype "passive"))
    )
    (net (code "55") (name "Net-(LED2-PadA)") (class "Default")
      (node (ref "LED2") (pin "A") (pinfunction "A_A") (pintype "passive"))
      (node (ref "R10") (pin "2") (pinfunction "2_2") (pintype "passive"))
    )
    (net (code "56") (name "Net-(LED3-PadC)") (class "Default")
      (node (ref "LED3") (pin "C") (pinfunction "C_C") (pintype "passive"))
      (node (ref "LED4") (pin "A") (pinfunction "A_A") (pintype "passive"))
      (node (ref "R4") (pin "2") (pinfunction "2_2") (pintype "passive"))
    )
    (net (code "57") (name "Net-(LED5-PadC)") (class "Default")
      (node (ref "LED5") (pin "C") (pinfunction "C_C") (pintype "passive"))
      (node (ref "LED6") (pin "A") (pinfunction "A_A") (pintype "passive"))
      (node (ref "R5") (pin "2") (pinfunction "2_2") (pintype "passive"))
    )
    (net (code "58") (name "Net-(MCU1-VREF_CMP)") (class "Default")
      (node (ref "JP29") (pin "2") (pinfunction "2_2") (pintype "passive"))
      (node (ref "MCU1") (pin "3") (pinfunction "VREF_CMP_3") (pintype "input"))
    )
    (net (code "59") (name "Net-(MCU1-XTALIN)") (class "Default")
      (node (ref "C2") (pin "1") (pinfunction "1_1") (pintype "passive"))
      (node (ref "MCU1") (pin "1") (pinfunction "XTALIN_1") (pintype "input"))
      (node (ref "Q1") (pin "2") (pinfunction "2_2") (pintype "passive"))
    )
    (net (code "60") (name "Net-(MCU1-XTALOUT)") (class "Default")
      (node (ref "C1") (pin "1") (pinfunction "1_1") (pintype "passive"))
      (node (ref "MCU1") (pin "2") (pinfunction "XTALOUT_2") (pintype "output"))
      (node (ref "Q1") (pin "1") (pinfunction "1_1") (pintype "passive"))
    )
    (net (code "61") (name "Net-(Q2-B)") (class "Default")
      (node (ref "Q2") (pin "1") (pinfunction "B_1") (pintype "passive"))
      (node (ref "R1") (pin "1") (pinfunction "1_1") (pintype "passive"))
    )
    (net (code "62") (name "Net-(Q2-C)") (class "Default")
      (node (ref "LED1") (pin "C") (pinfunction "C_C") (pintype "passive"))
      (node (ref "Q2") (pin "3") (pinfunction "C_3") (pintype "passive"))
    )
    (net (code "63") (name "Net-(Q3-B)") (class "Default")
      (node (ref "Q3") (pin "1") (pinfunction "B_1") (pintype "passive"))
      (node (ref "R11") (pin "1") (pinfunction "1_1") (pintype "passive"))
    )
    (net (code "64") (name "Net-(Q3-C)") (class "Default")
      (node (ref "LED2") (pin "C") (pinfunction "C_C") (pintype "passive"))
      (node (ref "Q3") (pin "3") (pinfunction "C_3") (pintype "passive"))
    )
    (net (code "65") (name "Net-(U1-HA)") (class "Default")
      (node (ref "R12") (pin "1") (pinfunction "1_1") (pintype "passive"))
      (node (ref "U1") (pin "1") (pinfunction "HA_1") (pintype "passive"))
      (node (ref "U1") (pin "4") (pinfunction "HB_4") (pintype "passive"))
    )
    (net (code "66") (name "Net-(U2-RC)") (class "Default")
      (node (ref "C3") (pin "1") (pinfunction "1_1") (pintype "passive"))
      (node (ref "R2") (pin "2") (pinfunction "2_2") (pintype "passive"))
      (node (ref "U2") (pin "3") (pinfunction "RC_3") (pintype "bidirectional"))
    )
    (net (code "67") (name "Net-(U3-RC)") (class "Default")
      (node (ref "C4") (pin "1") (pinfunction "1_1") (pintype "passive"))
      (node (ref "R3") (pin "2") (pinfunction "2_2") (pintype "passive"))
      (node (ref "U3") (pin "3") (pinfunction "RC_3") (pintype "bidirectional"))
    )
    (net (code "68") (name "VBB") (class "Default")
      (node (ref "C6") (pin "+") (pinfunction "+_+") (pintype "passive"))
      (node (ref "C7") (pin "+") (pinfunction "+_+") (pintype "passive"))
      (node (ref "JP5") (pin "2") (pinfunction "2_2") (pintype "passive"))
      (node (ref "JP8") (pin "1") (pinfunction "1_1") (pintype "passive"))
      (node (ref "JP8") (pin "2") (pinfunction "2_2") (pintype "passive"))
      (node (ref "JP8") (pin "3") (pinfunction "3_3") (pintype "passive"))
      (node (ref "JP8") (pin "4") (pinfunction "4_4") (pintype "passive"))
      (node (ref "JP9") (pin "1") (pinfunction "1_1") (pintype "passive"))
      (node (ref "JP9") (pin "2") (pinfunction "2_2") (pintype "passive"))
      (node (ref "JP9") (pin "3") (pinfunction "3_3") (pintype "passive"))
      (node (ref "JP9") (pin "4") (pinfunction "4_4") (pintype "passive"))
      (node (ref "U2") (pin "16") (pinfunction "VBB_16") (pintype "bidirectional"))
      (node (ref "U3") (pin "9") (pinfunction "VBB_9") (pintype "bidirectional"))
      (node (ref "X4") (pin "2") (pinfunction "2_2") (pintype "passive"))
      (node (ref "X5") (pin "1") (pinfunction "1_1") (pintype "passive"))
      (node (ref "X6") (pin "2") (pinfunction "2_2") (pintype "passive"))
    )
    (net (code "69") (name "VCC") (class "Default")
      (node (ref "C10") (pin "1") (pinfunction "1_1") (pintype "passive"))
      (node (ref "C11") (pin "1") (pinfunction "1_1") (pintype "passive"))
      (node (ref "C5") (pin "1") (pinfunction "1_1") (pintype "passive"))
      (node (ref "C8") (pin "1") (pinfunction "1_1") (pintype "passive"))
      (node (ref "C9") (pin "1") (pinfunction "1_1") (pintype "passive"))
      (node (ref "JP1") (pin "1") (pinfunction "1_1") (pintype "passive"))
      (node (ref "JP13") (pin "4") (pinfunction "4_4") (pintype "passive"))
      (node (ref "JP19") (pin "1") (pinfunction "1_1") (pintype "passive"))
      (node (ref "JP2") (pin "1") (pinfunction "1_1") (pintype "passive"))
      (node (ref "JP20") (pin "1") (pinfunction "1_1") (pintype "passive"))
      (node (ref "JP21") (pin "1") (pinfunction "1_1") (pintype "passive"))
      (node (ref "JP22") (pin "1") (pinfunction "1_1") (pintype "passive"))
      (node (ref "JP23") (pin "1") (pinfunction "1_1") (pintype "passive"))
      (node (ref "JP24") (pin "1") (pinfunction "1_1") (pintype "passive"))
      (node (ref "JP25") (pin "1") (pinfunction "1_1") (pintype "passive"))
      (node (ref "JP26") (pin "1") (pinfunction "1_1") (pintype "passive"))
      (node (ref "JP29") (pin "1") (pinfunction "1_1") (pintype "passive"))
      (node (ref "MCU1") (pin "44") (pinfunction "VCC_44") (pintype "power_in"))
      (node (ref "MCU1") (pin "47") (pinfunction "VCC_47") (pintype "power_in"))
      (node (ref "R10") (pin "1") (pinfunction "1_1") (pintype "passive"))
      (node (ref "R12") (pin "2") (pinfunction "2_2") (pintype "passive"))
      (node (ref "R13") (pin "2") (pinfunction "2_2") (pintype "passive"))
      (node (ref "R14") (pin "2") (pinfunction "2_2") (pintype "passive"))
      (node (ref "R15") (pin "2") (pinfunction "2_2") (pintype "passive"))
      (node (ref "R18") (pin "2") (pinfunction "2_2") (pintype "passive"))
      (node (ref "R6") (pin "1") (pinfunction "1_1") (pintype "passive"))
      (node (ref "R7") (pin "2") (pinfunction "2_2") (pintype "passive"))
      (node (ref "R8") (pin "2") (pinfunction "2_2") (pintype "passive"))
      (node (ref "R9") (pin "2") (pinfunction "2_2") (pintype "passive"))
      (node (ref "U1") (pin "14") (pinfunction "VCC_14") (pintype "power_in"))
      (node (ref "U2") (pin "6") (pinfunction "VCC_6") (pintype "power_in"))
      (node (ref "U3") (pin "6") (pinfunction "VCC_6") (pintype "power_in"))
      (node (ref "X1") (pin "3") (pinfunction "3_3") (pintype "passive"))
      (node (ref "X2") (pin "3") (pinfunction "3_3") (pintype "passive"))
    )
    (net (code "70") (name "VDD") (class "Default")
      (node (ref "JP14") (pin "1") (pinfunction "1_1") (pintype "passive"))
      (node (ref "JP15") (pin "1") (pinfunction "1_1") (pintype "passive"))
      (node (ref "JP27") (pin "1") (pinfunction "1_1") (pintype "passive"))
      (node (ref "JP28") (pin "1") (pinfunction "1_1") (pintype "passive"))
      (node (ref "R16") (pin "1") (pinfunction "1_1") (pintype "passive"))
      (node (ref "R17") (pin "1") (pinfunction "1_1") (pintype "passive"))
    )
    (net (code "71") (name "unconnected-(MCU1-RTCXIN-Pad46)") (class "Default")
      (node (ref "MCU1") (pin "46") (pinfunction "RTCXIN_46") (pintype "no_connect"))
    )
    (net (code "72") (name "unconnected-(MCU1-RTCXOUT-Pad45)") (class "Default")
      (node (ref "MCU1") (pin "45") (pinfunction "RTCXOUT_45") (pintype "no_connect"))
    )
    (net (code "73") (name "unconnected-(U2-VBB-Pad9)") (class "Default")
      (node (ref "U2") (pin "9") (pinfunction "VBB_9") (pintype "bidirectional"))
    )
    (net (code "74") (name "unconnected-(U3-VBB-Pad16)") (class "Default")
      (node (ref "U3") (pin "16") (pinfunction "VBB_16") (pintype "bidirectional"))
    )
  )
)
